# BLE_Development_Board_v2_2.net
KiCad netlist of a schematic drawn in EAGLE
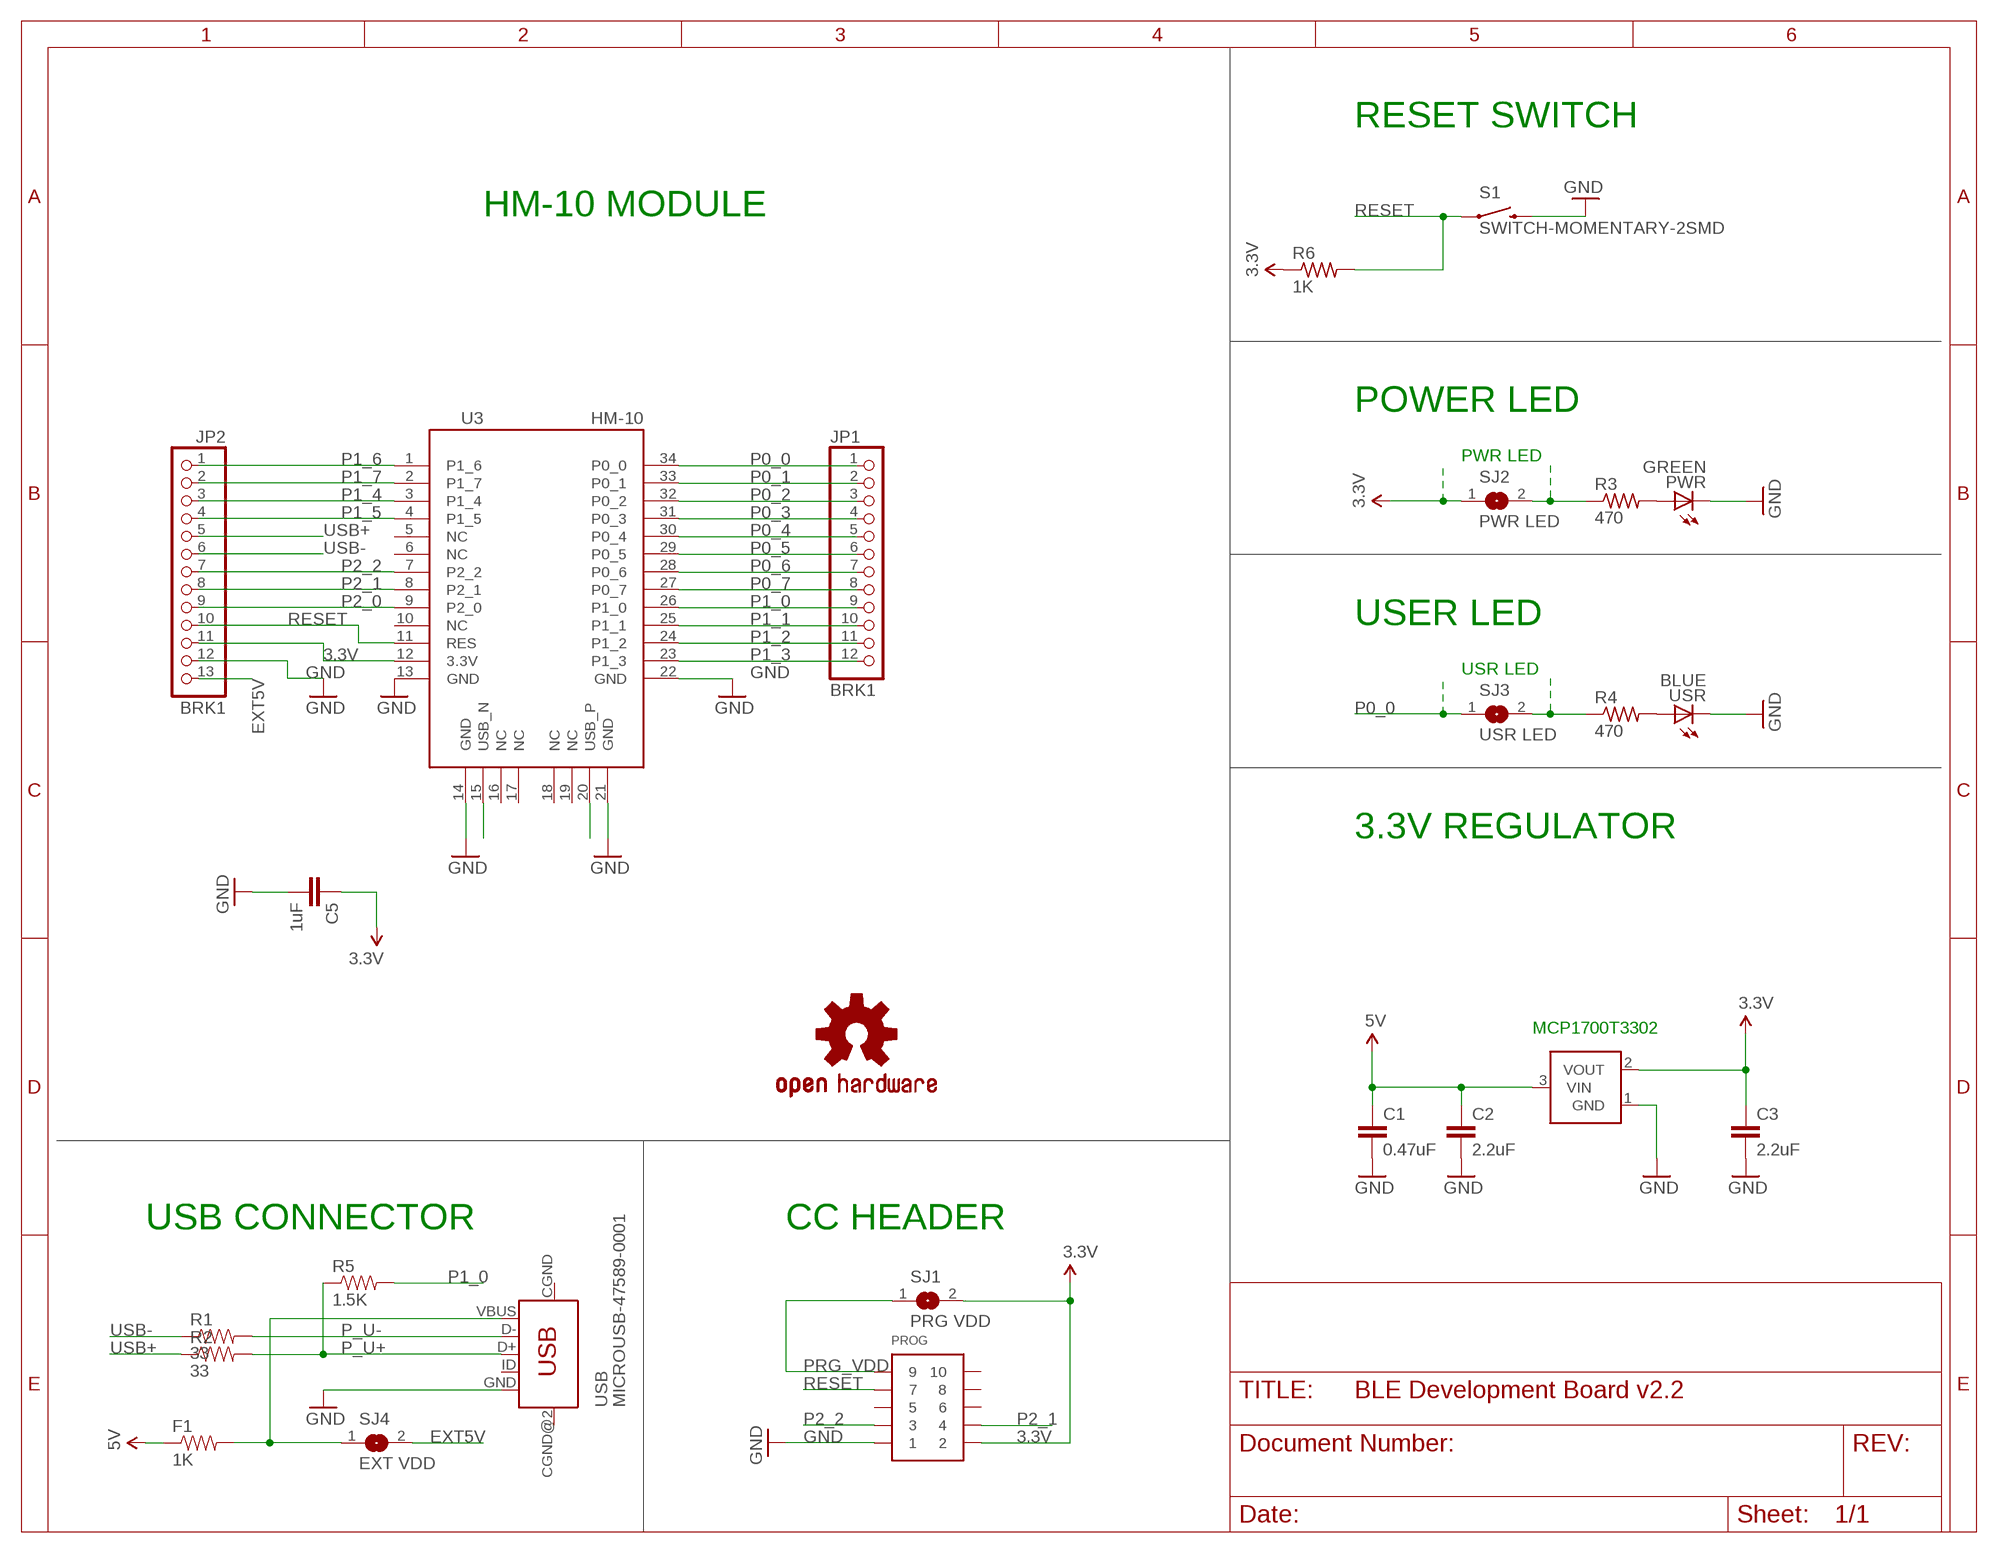
[diagram p0: schematic, sheet 1]

(export (version "E")
  (design (tool "Eeschema 10.0.6"))
  (components
    (comp (ref "C1")
      (value "0.47uF")
      (footprint "eagle-import:0603-CAP")
      (libsource (lib "eagle-import") (part "CAP0603-CAP"))
    )
    (comp (ref "C2")
      (value "2.2uF")
      (footprint "eagle-import:0603-CAP")
      (libsource (lib "eagle-import") (part "CAP0603-CAP"))
    )
    (comp (ref "C3")
      (value "2.2uF")
      (footprint "eagle-import:0603-CAP")
      (libsource (lib "eagle-import") (part "CAP0603-CAP"))
    )
    (comp (ref "C5")
      (value "1uF")
      (footprint "eagle-import:0603-CAP")
      (libsource (lib "eagle-import") (part "CAP0603-CAP"))
    )
    (comp (ref "F1")
      (value "1K")
      (footprint "eagle-import:0805")
      (libsource (lib "eagle-import") (part "RESISTOR0805-RES"))
    )
    (comp (ref "JP1")
      (value "BRK1")
      (footprint "eagle-import:1X12")
      (libsource (lib "eagle-import") (part "PINHD-1X12"))
    )
    (comp (ref "JP2")
      (value "BRK1")
      (footprint "eagle-import:1X13")
      (libsource (lib "eagle-import") (part "PINHD-1X13"))
    )
    (comp (ref "OSHW1")
      (value "OSHW-LOGOL")
      (footprint "eagle-import:OSHW-LOGO-L")
      (libsource (lib "eagle-import") (part "OSHW-LOGOL"))
    )
    (comp (ref "PROG")
      (value "CONN_5-2-FTSH-V")
      (footprint "eagle-import:FTSH-105-DV")
      (libsource (lib "eagle-import") (part "CONN_5-2-FTSH-V"))
    )
    (comp (ref "PWR")
      (value "GREEN")
      (footprint "eagle-import:CHIPLED_0603")
      (libsource (lib "eagle-import") (part "LEDCHIPLED_0603"))
    )
    (comp (ref "R1")
      (value "33")
      (footprint "eagle-import:0603-RES")
      (libsource (lib "eagle-import") (part "RESISTOR0603-RES"))
    )
    (comp (ref "R2")
      (value "33")
      (footprint "eagle-import:0603-RES")
      (libsource (lib "eagle-import") (part "RESISTOR0603-RES"))
    )
    (comp (ref "R3")
      (value "470")
      (footprint "eagle-import:R0603")
      (libsource (lib "eagle-import") (part "R-US_R0603"))
    )
    (comp (ref "R4")
      (value "470")
      (footprint "eagle-import:R0603")
      (libsource (lib "eagle-import") (part "R-US_R0603"))
    )
    (comp (ref "R5")
      (value "1.5K")
      (footprint "eagle-import:0603-RES")
      (libsource (lib "eagle-import") (part "RESISTOR0603-RES"))
    )
    (comp (ref "R6")
      (value "1K")
      (footprint "eagle-import:R0603")
      (libsource (lib "eagle-import") (part "R-US_R0603"))
    )
    (comp (ref "S1")
      (value "SWITCH-MOMENTARY-2SMD")
      (footprint "eagle-import:TACTILE_SWITCH_SMD")
      (libsource (lib "eagle-import") (part "SWITCH-MOMENTARY-2SMD"))
    )
    (comp (ref "SJ1")
      (value "PRG VDD")
      (footprint "eagle-import:SJ")
      (libsource (lib "eagle-import") (part "SJ"))
    )
    (comp (ref "SJ2")
      (value "PWR LED")
      (footprint "eagle-import:SJ")
      (libsource (lib "eagle-import") (part "SJ"))
    )
    (comp (ref "SJ3")
      (value "USR LED")
      (footprint "eagle-import:SJ")
      (libsource (lib "eagle-import") (part "SJ"))
    )
    (comp (ref "SJ4")
      (value "EXT VDD")
      (footprint "eagle-import:SJ")
      (libsource (lib "eagle-import") (part "SJ"))
    )
    (comp (ref "U2")
      (value "MCP1700")
      (footprint "eagle-import:SOT23-3")
      (libsource (lib "eagle-import") (part "MCP1700"))
    )
    (comp (ref "U3")
      (value "HM-10")
      (footprint "eagle-import:HM-10")
      (libsource (lib "eagle-import") (part "HM-10"))
    )
    (comp (ref "USB")
      (value "MICROUSB-47589-0001")
      (footprint "eagle-import:MICROUSB-47589-0001")
      (libsource (lib "eagle-import") (part "MICROUSB-47589-0001"))
    )
    (comp (ref "USR")
      (value "BLUE")
      (footprint "eagle-import:CHIPLED_0603")
      (libsource (lib "eagle-import") (part "LEDCHIPLED_0603"))
    )
  )
  (nets
    (net (code "1") (name "/EXT5V") (class "Default")
      (node (ref "JP2") (pin "13") (pinfunction "13_13") (pintype "passive"))
      (node (ref "SJ4") (pin "2") (pinfunction "2_2") (pintype "passive"))
    )
    (net (code "2") (name "/P0_0") (class "Default")
      (node (ref "JP1") (pin "1") (pinfunction "1_1") (pintype "passive"))
      (node (ref "SJ3") (pin "1") (pinfunction "1_1") (pintype "passive"))
      (node (ref "U3") (pin "34") (pinfunction "P0_0_34") (pintype "bidirectional"))
    )
    (net (code "3") (name "/P0_1") (class "Default")
      (node (ref "JP1") (pin "2") (pinfunction "2_2") (pintype "passive"))
      (node (ref "U3") (pin "33") (pinfunction "P0_1_33") (pintype "bidirectional"))
    )
    (net (code "4") (name "/P0_2") (class "Default")
      (node (ref "JP1") (pin "3") (pinfunction "3_3") (pintype "passive"))
      (node (ref "U3") (pin "32") (pinfunction "P0_2_32") (pintype "bidirectional"))
    )
    (net (code "5") (name "/P0_3") (class "Default")
      (node (ref "JP1") (pin "4") (pinfunction "4_4") (pintype "passive"))
      (node (ref "U3") (pin "31") (pinfunction "P0_3_31") (pintype "bidirectional"))
    )
    (net (code "6") (name "/P0_4") (class "Default")
      (node (ref "JP1") (pin "5") (pinfunction "5_5") (pintype "passive"))
      (node (ref "U3") (pin "30") (pinfunction "P0_4_30") (pintype "bidirectional"))
    )
    (net (code "7") (name "/P0_5") (class "Default")
      (node (ref "JP1") (pin "6") (pinfunction "6_6") (pintype "passive"))
      (node (ref "U3") (pin "29") (pinfunction "P0_5_29") (pintype "bidirectional"))
    )
    (net (code "8") (name "/P0_6") (class "Default")
      (node (ref "JP1") (pin "7") (pinfunction "7_7") (pintype "passive"))
      (node (ref "U3") (pin "28") (pinfunction "P0_6_28") (pintype "bidirectional"))
    )
    (net (code "9") (name "/P0_7") (class "Default")
      (node (ref "JP1") (pin "8") (pinfunction "8_8") (pintype "passive"))
      (node (ref "U3") (pin "27") (pinfunction "P0_7_27") (pintype "bidirectional"))
    )
    (net (code "10") (name "/P1_0") (class "Default")
      (node (ref "JP1") (pin "9") (pinfunction "9_9") (pintype "passive"))
      (node (ref "R5") (pin "2") (pinfunction "2_2") (pintype "passive"))
      (node (ref "U3") (pin "26") (pinfunction "P1_0_26") (pintype "bidirectional"))
    )
    (net (code "11") (name "/P1_1") (class "Default")
      (node (ref "JP1") (pin "10") (pinfunction "10_10") (pintype "passive"))
      (node (ref "U3") (pin "25") (pinfunction "P1_1_25") (pintype "bidirectional"))
    )
    (net (code "12") (name "/P1_2") (class "Default")
      (node (ref "JP1") (pin "11") (pinfunction "11_11") (pintype "passive"))
      (node (ref "U3") (pin "24") (pinfunction "P1_2_24") (pintype "bidirectional"))
    )
    (net (code "13") (name "/P1_3") (class "Default")
      (node (ref "JP1") (pin "12") (pinfunction "12_12") (pintype "passive"))
      (node (ref "U3") (pin "23") (pinfunction "P1_3_23") (pintype "bidirectional"))
    )
    (net (code "14") (name "/P1_4") (class "Default")
      (node (ref "JP2") (pin "3") (pinfunction "3_3") (pintype "passive"))
      (node (ref "U3") (pin "3") (pinfunction "P1_4_3") (pintype "bidirectional"))
    )
    (net (code "15") (name "/P1_5") (class "Default")
      (node (ref "JP2") (pin "4") (pinfunction "4_4") (pintype "passive"))
      (node (ref "U3") (pin "4") (pinfunction "P1_5_4") (pintype "bidirectional"))
    )
    (net (code "16") (name "/P1_6") (class "Default")
      (node (ref "JP2") (pin "1") (pinfunction "1_1") (pintype "passive"))
      (node (ref "U3") (pin "1") (pinfunction "P1_6_1") (pintype "bidirectional"))
    )
    (net (code "17") (name "/P1_7") (class "Default")
      (node (ref "JP2") (pin "2") (pinfunction "2_2") (pintype "passive"))
      (node (ref "U3") (pin "2") (pinfunction "P1_7_2") (pintype "bidirectional"))
    )
    (net (code "18") (name "/P2_0") (class "Default")
      (node (ref "JP2") (pin "9") (pinfunction "9_9") (pintype "passive"))
      (node (ref "U3") (pin "9") (pinfunction "P2_0_9") (pintype "bidirectional"))
    )
    (net (code "19") (name "/P2_1") (class "Default")
      (node (ref "JP2") (pin "8") (pinfunction "8_8") (pintype "passive"))
      (node (ref "PROG") (pin "4") (pinfunction "4_4") (pintype "bidirectional"))
      (node (ref "U3") (pin "8") (pinfunction "P2_1_8") (pintype "bidirectional"))
    )
    (net (code "20") (name "/P2_2") (class "Default")
      (node (ref "JP2") (pin "7") (pinfunction "7_7") (pintype "passive"))
      (node (ref "PROG") (pin "3") (pinfunction "3_3") (pintype "bidirectional"))
      (node (ref "U3") (pin "7") (pinfunction "P2_2_7") (pintype "bidirectional"))
    )
    (net (code "21") (name "/PRG_VDD") (class "Default")
      (node (ref "PROG") (pin "9") (pinfunction "9_9") (pintype "bidirectional"))
      (node (ref "SJ1") (pin "1") (pinfunction "1_1") (pintype "passive"))
    )
    (net (code "22") (name "/P_U+") (class "Default")
      (node (ref "R2") (pin "2") (pinfunction "2_2") (pintype "passive"))
      (node (ref "R5") (pin "1") (pinfunction "1_1") (pintype "passive"))
      (node (ref "USB") (pin "D+") (pinfunction "D+_D+") (pintype "bidirectional"))
    )
    (net (code "23") (name "/P_U-") (class "Default")
      (node (ref "R1") (pin "2") (pinfunction "2_2") (pintype "passive"))
      (node (ref "USB") (pin "D-") (pinfunction "D-_D-") (pintype "bidirectional"))
    )
    (net (code "24") (name "/RESET") (class "Default")
      (node (ref "JP2") (pin "10") (pinfunction "10_10") (pintype "passive"))
      (node (ref "PROG") (pin "7") (pinfunction "7_7") (pintype "bidirectional"))
      (node (ref "R6") (pin "2") (pinfunction "2_2") (pintype "passive"))
      (node (ref "S1") (pin "1") (pinfunction "1_1") (pintype "passive"))
      (node (ref "U3") (pin "11") (pinfunction "RES_11") (pintype "bidirectional"))
    )
    (net (code "25") (name "/USB+") (class "Default")
      (node (ref "JP2") (pin "5") (pinfunction "5_5") (pintype "passive"))
      (node (ref "R2") (pin "1") (pinfunction "1_1") (pintype "passive"))
      (node (ref "U3") (pin "20") (pinfunction "USB_P_20") (pintype "bidirectional"))
    )
    (net (code "26") (name "/USB-") (class "Default")
      (node (ref "JP2") (pin "6") (pinfunction "6_6") (pintype "passive"))
      (node (ref "R1") (pin "1") (pinfunction "1_1") (pintype "passive"))
      (node (ref "U3") (pin "15") (pinfunction "USB_N_15") (pintype "bidirectional"))
    )
    (net (code "27") (name "3.3V") (class "Default")
      (node (ref "C3") (pin "1") (pinfunction "1_1") (pintype "passive"))
      (node (ref "C5") (pin "1") (pinfunction "1_1") (pintype "passive"))
      (node (ref "JP2") (pin "11") (pinfunction "11_11") (pintype "passive"))
      (node (ref "PROG") (pin "2") (pinfunction "2_2") (pintype "bidirectional"))
      (node (ref "R6") (pin "1") (pinfunction "1_1") (pintype "passive"))
      (node (ref "SJ1") (pin "2") (pinfunction "2_2") (pintype "passive"))
      (node (ref "SJ2") (pin "1") (pinfunction "1_1") (pintype "passive"))
      (node (ref "U2") (pin "2") (pinfunction "VOUT_2") (pintype "power_in"))
      (node (ref "U3") (pin "12") (pinfunction "3.3V_12") (pintype "bidirectional"))
    )
    (net (code "28") (name "5V") (class "Default")
      (node (ref "C1") (pin "1") (pinfunction "1_1") (pintype "passive"))
      (node (ref "C2") (pin "1") (pinfunction "1_1") (pintype "passive"))
      (node (ref "F1") (pin "1") (pinfunction "1_1") (pintype "passive"))
      (node (ref "U2") (pin "3") (pinfunction "VIN_3") (pintype "power_in"))
    )
    (net (code "29") (name "GND") (class "Default")
      (node (ref "C1") (pin "2") (pinfunction "2_2") (pintype "passive"))
      (node (ref "C2") (pin "2") (pinfunction "2_2") (pintype "passive"))
      (node (ref "C3") (pin "2") (pinfunction "2_2") (pintype "passive"))
      (node (ref "C5") (pin "2") (pinfunction "2_2") (pintype "passive"))
      (node (ref "JP2") (pin "12") (pinfunction "12_12") (pintype "passive"))
      (node (ref "PROG") (pin "1") (pinfunction "1_1") (pintype "bidirectional"))
      (node (ref "PWR") (pin "C") (pinfunction "C_C") (pintype "passive"))
      (node (ref "S1") (pin "3") (pinfunction "2_3") (pintype "passive"))
      (node (ref "U2") (pin "1") (pinfunction "GND_1") (pintype "power_in"))
      (node (ref "U3") (pin "13") (pinfunction "GND_13") (pintype "bidirectional"))
      (node (ref "U3") (pin "14") (pinfunction "GND_14") (pintype "bidirectional"))
      (node (ref "U3") (pin "21") (pinfunction "GND_21") (pintype "bidirectional"))
      (node (ref "U3") (pin "22") (pinfunction "GND_22") (pintype "bidirectional"))
      (node (ref "USB") (pin "GND") (pinfunction "GND_GND") (pintype "bidirectional"))
      (node (ref "USR") (pin "C") (pinfunction "C_C") (pintype "passive"))
    )
    (net (code "30") (name "Net-(F1-Pad2)") (class "Default")
      (node (ref "F1") (pin "2") (pinfunction "2_2") (pintype "passive"))
      (node (ref "SJ4") (pin "1") (pinfunction "1_1") (pintype "passive"))
      (node (ref "USB") (pin "VBUS") (pinfunction "VBUS_VBUS") (pintype "bidirectional"))
    )
    (net (code "31") (name "Net-(PWR-PadA)") (class "Default")
      (node (ref "PWR") (pin "A") (pinfunction "A_A") (pintype "passive"))
      (node (ref "R3") (pin "2") (pinfunction "2_2") (pintype "passive"))
    )
    (net (code "32") (name "Net-(R3-Pad1)") (class "Default")
      (node (ref "R3") (pin "1") (pinfunction "1_1") (pintype "passive"))
      (node (ref "SJ2") (pin "2") (pinfunction "2_2") (pintype "passive"))
    )
    (net (code "33") (name "Net-(R4-Pad1)") (class "Default")
      (node (ref "R4") (pin "1") (pinfunction "1_1") (pintype "passive"))
      (node (ref "SJ3") (pin "2") (pinfunction "2_2") (pintype "passive"))
    )
    (net (code "34") (name "Net-(R4-Pad2)") (class "Default")
      (node (ref "R4") (pin "2") (pinfunction "2_2") (pintype "passive"))
      (node (ref "USR") (pin "A") (pinfunction "A_A") (pintype "passive"))
    )
    (net (code "35") (name "unconnected-(PROG-Pad5)") (class "Default")
      (node (ref "PROG") (pin "5") (pinfunction "5_5") (pintype "bidirectional"))
    )
    (net (code "36") (name "unconnected-(PROG-Pad6)") (class "Default")
      (node (ref "PROG") (pin "6") (pinfunction "6_6") (pintype "bidirectional"))
    )
    (net (code "37") (name "unconnected-(PROG-Pad8)") (class "Default")
      (node (ref "PROG") (pin "8") (pinfunction "8_8") (pintype "bidirectional"))
    )
    (net (code "38") (name "unconnected-(PROG-Pad10)") (class "Default")
      (node (ref "PROG") (pin "10") (pinfunction "10_10") (pintype "bidirectional"))
    )
    (net (code "39") (name "unconnected-(U3-NC-Pad5)") (class "Default")
      (node (ref "U3") (pin "5") (pinfunction "NC_5") (pintype "bidirectional"))
    )
    (net (code "40") (name "unconnected-(U3-NC-Pad6)") (class "Default")
      (node (ref "U3") (pin "6") (pinfunction "NC_6") (pintype "bidirectional"))
    )
    (net (code "41") (name "unconnected-(U3-NC-Pad10)") (class "Default")
      (node (ref "U3") (pin "10") (pinfunction "NC_10") (pintype "bidirectional"))
    )
    (net (code "42") (name "unconnected-(U3-NC-Pad16)") (class "Default")
      (node (ref "U3") (pin "16") (pinfunction "NC_16") (pintype "bidirectional"))
    )
    (net (code "43") (name "unconnected-(U3-NC-Pad17)") (class "Default")
      (node (ref "U3") (pin "17") (pinfunction "NC_17") (pintype "bidirectional"))
    )
    (net (code "44") (name "unconnected-(U3-NC-Pad18)") (class "Default")
      (node (ref "U3") (pin "18") (pinfunction "NC_18") (pintype "bidirectional"))
    )
    (net (code "45") (name "unconnected-(U3-NC-Pad19)") (class "Default")
      (node (ref "U3") (pin "19") (pinfunction "NC_19") (pintype "bidirectional"))
    )
    (net (code "46") (name "unconnected-(USB-MTN2-PadCGND)") (class "Default")
      (node (ref "USB") (pin "CGND") (pinfunction "MTN2_CGND") (pintype "bidirectional"))
    )
    (net (code "47") (name "unconnected-(USB-MTN4-PadCGND@2)") (class "Default")
      (node (ref "USB") (pin "CGND@2") (pinfunction "MTN4_CGND@2") (pintype "bidirectional"))
    )
    (net (code "48") (name "unconnected-(USB-PadID)") (class "Default")
      (node (ref "USB") (pin "ID") (pinfunction "ID_ID") (pintype "bidirectional"))
    )
  )
)
